# shaki_rev_a.net
KiCad netlist of a schematic drawn in EAGLE
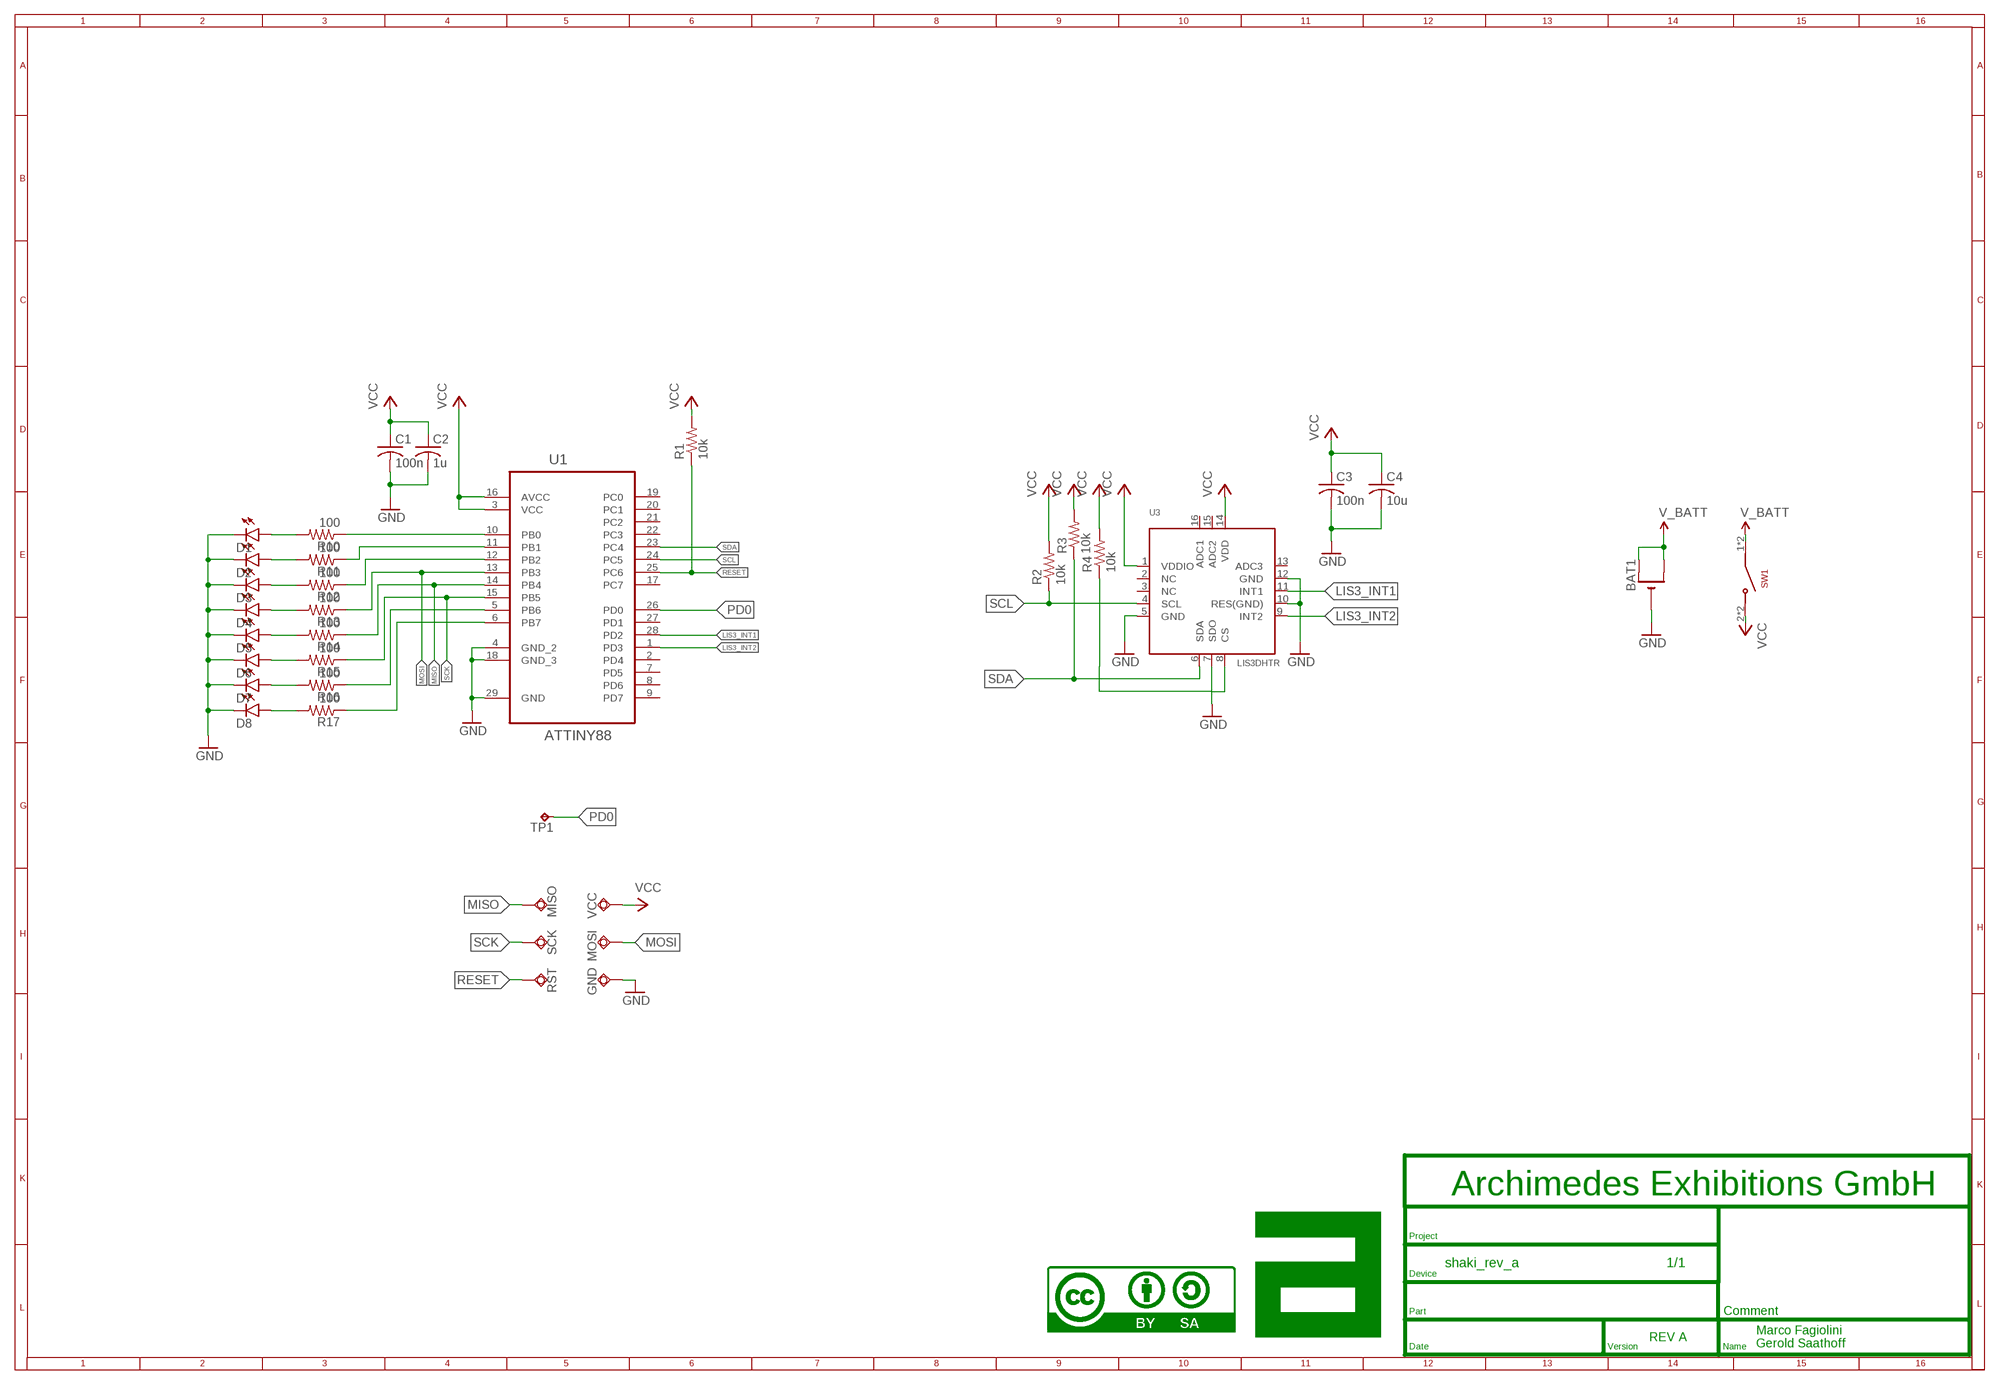
[diagram p0: schematic, sheet 1]

(export (version "E")
  (design (tool "Eeschema 10.0.6"))
  (components
    (comp (ref "BAT1")
      (value "CR1220SMT")
      (footprint "eagle-import:CR1220-SMD")
      (libsource (lib "eagle-import") (part "CR1220SMT"))
    )
    (comp (ref "C1")
      (value "100n")
      (footprint "eagle-import:C0603K")
      (libsource (lib "eagle-import") (part "C-USC0603K"))
    )
    (comp (ref "C2")
      (value "1u")
      (footprint "eagle-import:C0603K")
      (libsource (lib "eagle-import") (part "C-USC0603K"))
    )
    (comp (ref "C3")
      (value "100n")
      (footprint "eagle-import:C0603K")
      (libsource (lib "eagle-import") (part "C-USC0603K"))
    )
    (comp (ref "C4")
      (value "10u")
      (footprint "eagle-import:C0603K")
      (libsource (lib "eagle-import") (part "C-USC0603K"))
    )
    (comp (ref "D1")
      (value "LED0603")
      (footprint "eagle-import:LED-0603")
      (libsource (lib "eagle-import") (part "LED0603"))
    )
    (comp (ref "D2")
      (value "LED0603")
      (footprint "eagle-import:LED-0603")
      (libsource (lib "eagle-import") (part "LED0603"))
    )
    (comp (ref "D3")
      (value "LED0603")
      (footprint "eagle-import:LED-0603")
      (libsource (lib "eagle-import") (part "LED0603"))
    )
    (comp (ref "D4")
      (value "LED0603")
      (footprint "eagle-import:LED-0603")
      (libsource (lib "eagle-import") (part "LED0603"))
    )
    (comp (ref "D5")
      (value "LED0603")
      (footprint "eagle-import:LED-0603")
      (libsource (lib "eagle-import") (part "LED0603"))
    )
    (comp (ref "D6")
      (value "LED0603")
      (footprint "eagle-import:LED-0603")
      (libsource (lib "eagle-import") (part "LED0603"))
    )
    (comp (ref "D7")
      (value "LED0603")
      (footprint "eagle-import:LED-0603")
      (libsource (lib "eagle-import") (part "LED0603"))
    )
    (comp (ref "D8")
      (value "LED0603")
      (footprint "eagle-import:LED-0603")
      (libsource (lib "eagle-import") (part "LED0603"))
    )
    (comp (ref "GND")
      (value "TPSQTP13R")
      (footprint "eagle-import:TP13R")
      (libsource (lib "eagle-import") (part "TPSQTP13R"))
    )
    (comp (ref "MISO")
      (value "TPSQTP13R")
      (footprint "eagle-import:TP13R")
      (libsource (lib "eagle-import") (part "TPSQTP13R"))
    )
    (comp (ref "MOSI")
      (value "TPSQTP13R")
      (footprint "eagle-import:TP13R")
      (libsource (lib "eagle-import") (part "TPSQTP13R"))
    )
    (comp (ref "R1")
      (value "10k")
      (footprint "eagle-import:0603")
      (libsource (lib "eagle-import") (part "0.05OHM-1/5W-1%(0603)"))
    )
    (comp (ref "R2")
      (value "10k")
      (footprint "eagle-import:0603")
      (libsource (lib "eagle-import") (part "0.05OHM-1/5W-1%(0603)"))
    )
    (comp (ref "R3")
      (value "10k")
      (footprint "eagle-import:0603")
      (libsource (lib "eagle-import") (part "0.05OHM-1/5W-1%(0603)"))
    )
    (comp (ref "R4")
      (value "10k")
      (footprint "eagle-import:0603")
      (libsource (lib "eagle-import") (part "0.05OHM-1/5W-1%(0603)"))
    )
    (comp (ref "R10")
      (value "100")
      (footprint "eagle-import:0603")
      (libsource (lib "eagle-import") (part "0.05OHM-1/5W-1%(0603)"))
    )
    (comp (ref "R11")
      (value "100")
      (footprint "eagle-import:0603")
      (libsource (lib "eagle-import") (part "0.05OHM-1/5W-1%(0603)"))
    )
    (comp (ref "R12")
      (value "100")
      (footprint "eagle-import:0603")
      (libsource (lib "eagle-import") (part "0.05OHM-1/5W-1%(0603)"))
    )
    (comp (ref "R13")
      (value "100")
      (footprint "eagle-import:0603")
      (libsource (lib "eagle-import") (part "0.05OHM-1/5W-1%(0603)"))
    )
    (comp (ref "R14")
      (value "100")
      (footprint "eagle-import:0603")
      (libsource (lib "eagle-import") (part "0.05OHM-1/5W-1%(0603)"))
    )
    (comp (ref "R15")
      (value "100")
      (footprint "eagle-import:0603")
      (libsource (lib "eagle-import") (part "0.05OHM-1/5W-1%(0603)"))
    )
    (comp (ref "R16")
      (value "100")
      (footprint "eagle-import:0603")
      (libsource (lib "eagle-import") (part "0.05OHM-1/5W-1%(0603)"))
    )
    (comp (ref "R17")
      (value "100")
      (footprint "eagle-import:0603")
      (libsource (lib "eagle-import") (part "0.05OHM-1/5W-1%(0603)"))
    )
    (comp (ref "RST")
      (value "TPSQTP13R")
      (footprint "eagle-import:TP13R")
      (libsource (lib "eagle-import") (part "TPSQTP13R"))
    )
    (comp (ref "SCK")
      (value "TPSQTP13R")
      (footprint "eagle-import:TP13R")
      (libsource (lib "eagle-import") (part "TPSQTP13R"))
    )
    (comp (ref "SW1")
      (value "SKRRABE010")
      (footprint "eagle-import:SKRRABE010")
      (libsource (lib "eagle-import") (part "SKRRABE010"))
    )
    (comp (ref "TP1")
      (value "TESTPAD")
      (footprint "eagle-import:TESTPAD")
      (libsource (lib "eagle-import") (part "TESTPAD"))
    )
    (comp (ref "U1")
      (value "ATTINY88")
      (footprint "eagle-import:QFN45P400X400X100-29N")
      (fields (field (name "MPN") "ATTINY48-MMU"))
      (libsource (lib "eagle-import") (part "ATTINY48-MMU"))
    )
    (comp (ref "U3")
      (value "LIS3DHTR")
      (footprint "eagle-import:LGA16_3X3MM")
      (libsource (lib "eagle-import") (part "ACCEL_LIS3DHTR"))
    )
    (comp (ref "VCC")
      (value "TPSQTP13R")
      (footprint "eagle-import:TP13R")
      (libsource (lib "eagle-import") (part "TPSQTP13R"))
    )
  )
  (nets
    (net (code "1") (name "GND") (class "Default")
      (node (ref "BAT1") (pin "-") (pinfunction "-_-") (pintype "passive"))
      (node (ref "C1") (pin "2") (pinfunction "2_2") (pintype "passive"))
      (node (ref "C2") (pin "2") (pinfunction "2_2") (pintype "passive"))
      (node (ref "C3") (pin "2") (pinfunction "2_2") (pintype "passive"))
      (node (ref "C4") (pin "2") (pinfunction "2_2") (pintype "passive"))
      (node (ref "D1") (pin "C") (pinfunction "C_C") (pintype "passive"))
      (node (ref "D2") (pin "C") (pinfunction "C_C") (pintype "passive"))
      (node (ref "D3") (pin "C") (pinfunction "C_C") (pintype "passive"))
      (node (ref "D4") (pin "C") (pinfunction "C_C") (pintype "passive"))
      (node (ref "D5") (pin "C") (pinfunction "C_C") (pintype "passive"))
      (node (ref "D6") (pin "C") (pinfunction "C_C") (pintype "passive"))
      (node (ref "D7") (pin "C") (pinfunction "C_C") (pintype "passive"))
      (node (ref "D8") (pin "C") (pinfunction "C_C") (pintype "passive"))
      (node (ref "GND") (pin "TP") (pinfunction "TP_TP") (pintype "input"))
      (node (ref "U1") (pin "18") (pinfunction "GND_3_18") (pintype "power_in"))
      (node (ref "U1") (pin "29") (pinfunction "GND_29") (pintype "power_in"))
      (node (ref "U1") (pin "4") (pinfunction "GND_2_4") (pintype "power_in"))
      (node (ref "U3") (pin "10") (pinfunction "RES(GND)_10") (pintype "bidirectional"))
      (node (ref "U3") (pin "12") (pinfunction "GND_12") (pintype "power_in"))
      (node (ref "U3") (pin "5") (pinfunction "GND_5") (pintype "power_in"))
      (node (ref "U3") (pin "7") (pinfunction "SDO_7") (pintype "bidirectional"))
    )
    (net (code "2") (name "LIS3_INT1") (class "Default")
      (node (ref "U1") (pin "28") (pinfunction "PD2_28") (pintype "bidirectional"))
      (node (ref "U3") (pin "11") (pinfunction "INT1_11") (pintype "output"))
    )
    (net (code "3") (name "LIS3_INT2") (class "Default")
      (node (ref "U1") (pin "1") (pinfunction "PD3_1") (pintype "bidirectional"))
      (node (ref "U3") (pin "9") (pinfunction "INT2_9") (pintype "output"))
    )
    (net (code "4") (name "MISO") (class "Default")
      (node (ref "MISO") (pin "TP") (pinfunction "TP_TP") (pintype "input"))
      (node (ref "R14") (pin "1") (pinfunction "1_1") (pintype "passive"))
      (node (ref "U1") (pin "14") (pinfunction "PB4_14") (pintype "bidirectional"))
    )
    (net (code "5") (name "MOSI") (class "Default")
      (node (ref "MOSI") (pin "TP") (pinfunction "TP_TP") (pintype "input"))
      (node (ref "R13") (pin "1") (pinfunction "1_1") (pintype "passive"))
      (node (ref "U1") (pin "13") (pinfunction "PB3_13") (pintype "bidirectional"))
    )
    (net (code "6") (name "Net-(D1-PadA)") (class "Default")
      (node (ref "D1") (pin "A") (pinfunction "A_A") (pintype "passive"))
      (node (ref "R10") (pin "2") (pinfunction "2_2") (pintype "passive"))
    )
    (net (code "7") (name "Net-(D2-PadA)") (class "Default")
      (node (ref "D2") (pin "A") (pinfunction "A_A") (pintype "passive"))
      (node (ref "R11") (pin "2") (pinfunction "2_2") (pintype "passive"))
    )
    (net (code "8") (name "Net-(D3-PadA)") (class "Default")
      (node (ref "D3") (pin "A") (pinfunction "A_A") (pintype "passive"))
      (node (ref "R12") (pin "2") (pinfunction "2_2") (pintype "passive"))
    )
    (net (code "9") (name "Net-(D4-PadA)") (class "Default")
      (node (ref "D4") (pin "A") (pinfunction "A_A") (pintype "passive"))
      (node (ref "R13") (pin "2") (pinfunction "2_2") (pintype "passive"))
    )
    (net (code "10") (name "Net-(D5-PadA)") (class "Default")
      (node (ref "D5") (pin "A") (pinfunction "A_A") (pintype "passive"))
      (node (ref "R14") (pin "2") (pinfunction "2_2") (pintype "passive"))
    )
    (net (code "11") (name "Net-(D6-PadA)") (class "Default")
      (node (ref "D6") (pin "A") (pinfunction "A_A") (pintype "passive"))
      (node (ref "R15") (pin "2") (pinfunction "2_2") (pintype "passive"))
    )
    (net (code "12") (name "Net-(D7-PadA)") (class "Default")
      (node (ref "D7") (pin "A") (pinfunction "A_A") (pintype "passive"))
      (node (ref "R16") (pin "2") (pinfunction "2_2") (pintype "passive"))
    )
    (net (code "13") (name "Net-(D8-PadA)") (class "Default")
      (node (ref "D8") (pin "A") (pinfunction "A_A") (pintype "passive"))
      (node (ref "R17") (pin "2") (pinfunction "2_2") (pintype "passive"))
    )
    (net (code "14") (name "Net-(U1-PB0)") (class "Default")
      (node (ref "R10") (pin "1") (pinfunction "1_1") (pintype "passive"))
      (node (ref "U1") (pin "10") (pinfunction "PB0_10") (pintype "bidirectional"))
    )
    (net (code "15") (name "Net-(U1-PB1)") (class "Default")
      (node (ref "R11") (pin "1") (pinfunction "1_1") (pintype "passive"))
      (node (ref "U1") (pin "11") (pinfunction "PB1_11") (pintype "bidirectional"))
    )
    (net (code "16") (name "Net-(U1-PB2)") (class "Default")
      (node (ref "R12") (pin "1") (pinfunction "1_1") (pintype "passive"))
      (node (ref "U1") (pin "12") (pinfunction "PB2_12") (pintype "bidirectional"))
    )
    (net (code "17") (name "Net-(U1-PB6)") (class "Default")
      (node (ref "R16") (pin "1") (pinfunction "1_1") (pintype "passive"))
      (node (ref "U1") (pin "5") (pinfunction "PB6_5") (pintype "bidirectional"))
    )
    (net (code "18") (name "Net-(U1-PB7)") (class "Default")
      (node (ref "R17") (pin "1") (pinfunction "1_1") (pintype "passive"))
      (node (ref "U1") (pin "6") (pinfunction "PB7_6") (pintype "bidirectional"))
    )
    (net (code "19") (name "Net-(U3-CS)") (class "Default")
      (node (ref "R4") (pin "1") (pinfunction "1_1") (pintype "passive"))
      (node (ref "U3") (pin "8") (pinfunction "CS_8") (pintype "input"))
    )
    (net (code "20") (name "PD0") (class "Default")
      (node (ref "TP1") (pin "P$1") (pinfunction "TP_P$1") (pintype "input"))
      (node (ref "U1") (pin "26") (pinfunction "PD0_26") (pintype "bidirectional"))
    )
    (net (code "21") (name "RESET") (class "Default")
      (node (ref "R1") (pin "1") (pinfunction "1_1") (pintype "passive"))
      (node (ref "RST") (pin "TP") (pinfunction "TP_TP") (pintype "input"))
      (node (ref "U1") (pin "25") (pinfunction "PC6_25") (pintype "bidirectional"))
    )
    (net (code "22") (name "SCK") (class "Default")
      (node (ref "R15") (pin "1") (pinfunction "1_1") (pintype "passive"))
      (node (ref "SCK") (pin "TP") (pinfunction "TP_TP") (pintype "input"))
      (node (ref "U1") (pin "15") (pinfunction "PB5_15") (pintype "bidirectional"))
    )
    (net (code "23") (name "SCL") (class "Default")
      (node (ref "R2") (pin "1") (pinfunction "1_1") (pintype "passive"))
      (node (ref "U1") (pin "24") (pinfunction "PC5_24") (pintype "bidirectional"))
      (node (ref "U3") (pin "4") (pinfunction "SCL_4") (pintype "bidirectional"))
    )
    (net (code "24") (name "SDA") (class "Default")
      (node (ref "R3") (pin "1") (pinfunction "1_1") (pintype "passive"))
      (node (ref "U1") (pin "23") (pinfunction "PC4_23") (pintype "bidirectional"))
      (node (ref "U3") (pin "6") (pinfunction "SDA_6") (pintype "bidirectional"))
    )
    (net (code "25") (name "VCC") (class "Default")
      (node (ref "C1") (pin "1") (pinfunction "1_1") (pintype "passive"))
      (node (ref "C2") (pin "1") (pinfunction "1_1") (pintype "passive"))
      (node (ref "C3") (pin "1") (pinfunction "1_1") (pintype "passive"))
      (node (ref "C4") (pin "1") (pinfunction "1_1") (pintype "passive"))
      (node (ref "R1") (pin "2") (pinfunction "2_2") (pintype "passive"))
      (node (ref "R2") (pin "2") (pinfunction "2_2") (pintype "passive"))
      (node (ref "R3") (pin "2") (pinfunction "2_2") (pintype "passive"))
      (node (ref "R4") (pin "2") (pinfunction "2_2") (pintype "passive"))
      (node (ref "SW1") (pin "2") (pinfunction "2_2") (pintype "bidirectional"))
      (node (ref "SW1") (pin "4") (pinfunction "2_4") (pintype "bidirectional"))
      (node (ref "U1") (pin "16") (pinfunction "AVCC_16") (pintype "power_in"))
      (node (ref "U1") (pin "3") (pinfunction "VCC_3") (pintype "power_in"))
      (node (ref "U3") (pin "1") (pinfunction "VDDIO_1") (pintype "power_in"))
      (node (ref "U3") (pin "14") (pinfunction "VDD_14") (pintype "power_in"))
      (node (ref "VCC") (pin "TP") (pinfunction "TP_TP") (pintype "input"))
    )
    (net (code "26") (name "V_BATT") (class "Default")
      (node (ref "BAT1") (pin "+$1") (pinfunction "+_+$1") (pintype "passive"))
      (node (ref "BAT1") (pin "+$2") (pinfunction "+1_+$2") (pintype "passive"))
      (node (ref "SW1") (pin "1") (pinfunction "1_1") (pintype "bidirectional"))
      (node (ref "SW1") (pin "3") (pinfunction "1_3") (pintype "bidirectional"))
    )
    (net (code "27") (name "unconnected-(U1-PC0-Pad19)") (class "Default")
      (node (ref "U1") (pin "19") (pinfunction "PC0_19") (pintype "bidirectional"))
    )
    (net (code "28") (name "unconnected-(U1-PC1-Pad20)") (class "Default")
      (node (ref "U1") (pin "20") (pinfunction "PC1_20") (pintype "bidirectional"))
    )
    (net (code "29") (name "unconnected-(U1-PC2-Pad21)") (class "Default")
      (node (ref "U1") (pin "21") (pinfunction "PC2_21") (pintype "bidirectional"))
    )
    (net (code "30") (name "unconnected-(U1-PC3-Pad22)") (class "Default")
      (node (ref "U1") (pin "22") (pinfunction "PC3_22") (pintype "bidirectional"))
    )
    (net (code "31") (name "unconnected-(U1-PC7-Pad17)") (class "Default")
      (node (ref "U1") (pin "17") (pinfunction "PC7_17") (pintype "bidirectional"))
    )
    (net (code "32") (name "unconnected-(U1-PD1-Pad27)") (class "Default")
      (node (ref "U1") (pin "27") (pinfunction "PD1_27") (pintype "bidirectional"))
    )
    (net (code "33") (name "unconnected-(U1-PD4-Pad2)") (class "Default")
      (node (ref "U1") (pin "2") (pinfunction "PD4_2") (pintype "bidirectional"))
    )
    (net (code "34") (name "unconnected-(U1-PD5-Pad7)") (class "Default")
      (node (ref "U1") (pin "7") (pinfunction "PD5_7") (pintype "bidirectional"))
    )
    (net (code "35") (name "unconnected-(U1-PD6-Pad8)") (class "Default")
      (node (ref "U1") (pin "8") (pinfunction "PD6_8") (pintype "bidirectional"))
    )
    (net (code "36") (name "unconnected-(U1-PD7-Pad9)") (class "Default")
      (node (ref "U1") (pin "9") (pinfunction "PD7_9") (pintype "bidirectional"))
    )
    (net (code "37") (name "unconnected-(U3-ADC1-Pad16)") (class "Default")
      (node (ref "U3") (pin "16") (pinfunction "ADC1_16") (pintype "input"))
    )
    (net (code "38") (name "unconnected-(U3-ADC2-Pad15)") (class "Default")
      (node (ref "U3") (pin "15") (pinfunction "ADC2_15") (pintype "input"))
    )
    (net (code "39") (name "unconnected-(U3-ADC3-Pad13)") (class "Default")
      (node (ref "U3") (pin "13") (pinfunction "ADC3_13") (pintype "input"))
    )
    (net (code "40") (name "unconnected-(U3-NC-Pad2)") (class "Default")
      (node (ref "U3") (pin "2") (pinfunction "NC_2") (pintype "no_connect"))
    )
    (net (code "41") (name "unconnected-(U3-NC-Pad3)") (class "Default")
      (node (ref "U3") (pin "3") (pinfunction "NC_3") (pintype "no_connect"))
    )
  )
)
